# STB_FanControl.net
KiCad netlist of a schematic drawn in Altium Designer
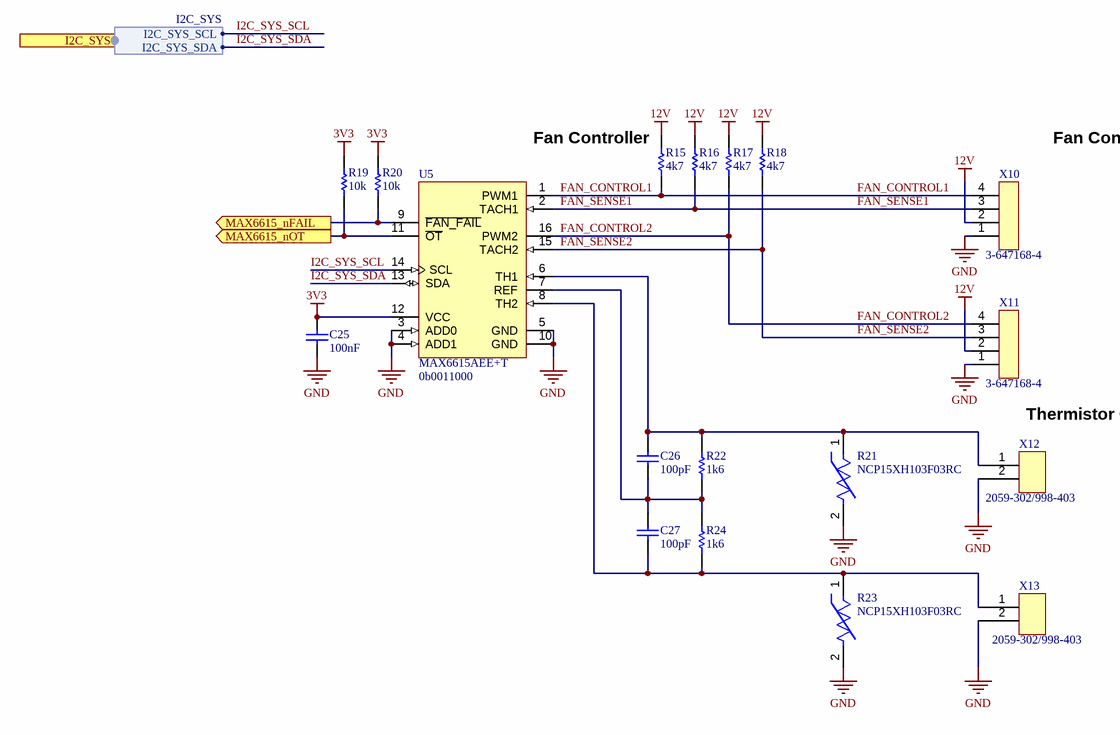
[diagram p0: STB_FanControl.SchDoc]

(export (version "E")
  (design (tool "Eeschema 10.0.6"))
  (components
    (comp (ref "C25")
      (value "100nF")
      (footprint "CAPC1050X55X23LL05T13")
      (description "Chip Capacitor, 100 nF, +/- 10%, 16 V, -55 to 125 degC, 0402 (1005 Metric), RoHS, Tape and Reel")
      (fields
        (field (name "MANUFACTURER") "Samsung Electro-Mechanics")
        (field (name "MANUFACTURER PART NUMBER") "CL05B104KO5NNNC")
      )
      (libsource (lib "Altium Content Vault") (part "CAP-NP-2"))
    )
    (comp (ref "C26")
      (value "100pF")
      (footprint "CAPC1005X56X25LL10T15")
      (fields
        (field (name "MANUFACTURER") "AVX Interconnect / Elco")
        (field (name "PART NUMBER") "04023A101KAT2A")
      )
      (libsource (lib "Altium Content Vault") (part "CAP"))
    )
    (comp (ref "C27")
      (value "100pF")
      (footprint "CAPC1005X56X25LL10T15")
      (fields
        (field (name "MANUFACTURER") "AVX Interconnect / Elco")
        (field (name "PART NUMBER") "04023A101KAT2A")
      )
      (libsource (lib "Altium Content Vault") (part "CAP"))
    )
    (comp (ref "R15")
      (value "4k7")
      (footprint "RESC1005X40X25LL05T10")
      (fields
        (field (name "MANUFACTURER") "Yageo / Phycomp")
        (field (name "PART NUMBER") "RC0402FR-074K7L")
        (field (name "TOLERANCE") "1%")
      )
      (libsource (lib "Altium Content Vault") (part "RES"))
    )
    (comp (ref "R16")
      (value "4k7")
      (footprint "RESC1005X40X25LL05T10")
      (fields
        (field (name "MANUFACTURER") "Yageo / Phycomp")
        (field (name "PART NUMBER") "RC0402FR-074K7L")
        (field (name "TOLERANCE") "1%")
      )
      (libsource (lib "Altium Content Vault") (part "RES"))
    )
    (comp (ref "R17")
      (value "4k7")
      (footprint "RESC1005X40X25LL05T10")
      (fields
        (field (name "MANUFACTURER") "Yageo / Phycomp")
        (field (name "PART NUMBER") "RC0402FR-074K7L")
        (field (name "TOLERANCE") "1%")
      )
      (libsource (lib "Altium Content Vault") (part "RES"))
    )
    (comp (ref "R18")
      (value "4k7")
      (footprint "RESC1005X40X25LL05T10")
      (fields
        (field (name "MANUFACTURER") "Yageo / Phycomp")
        (field (name "PART NUMBER") "RC0402FR-074K7L")
        (field (name "TOLERANCE") "1%")
      )
      (libsource (lib "Altium Content Vault") (part "RES"))
    )
    (comp (ref "R19")
      (value "10k")
      (footprint "RESC1005X40X25LL05T05")
      (description "Chip Resistor, 10 KOhm, +/- 1%, 0.1 W, -55 to 155 degC, 0402 (1005 Metric), RoHS, Tape and Reel")
      (fields (field (name "TOLERANCE") "1%") (field (name "MANUFACTURER") "Panasonic"))
      (libsource (lib "Altium Content Vault") (part "RES-2"))
    )
    (comp (ref "R20")
      (value "10k")
      (footprint "RESC1005X40X25LL05T05")
      (description "Chip Resistor, 10 KOhm, +/- 1%, 0.1 W, -55 to 155 degC, 0402 (1005 Metric), RoHS, Tape and Reel")
      (fields (field (name "TOLERANCE") "1%") (field (name "MANUFACTURER") "Panasonic"))
      (libsource (lib "Altium Content Vault") (part "RES-2"))
    )
    (comp (ref "R21")
      (value "NCP15XH103F03RC")
      (footprint "FP-NCP15-NCU15-0_05-IPC_C")
      (description "NTC Thermistor for Temperature Sensor, 0402, 10kΩ, 1%, 0.1mA, 5V")
      (fields (field (name "TOLERANCE") "1%") (field (name "MANUFACTURER") "Murata"))
      (libsource (lib "Altium Content Vault") (part "3b148a6ebabc5fb4d708a66c052d352"))
    )
    (comp (ref "R22")
      (value "1k6")
      (footprint "RESC1005X40X25LL05T10")
      (fields
        (field (name "MANUFACTURER") "Yageo / Phycomp")
        (field (name "PART NUMBER") "RC0402FR-071K6L")
        (field (name "TOLERANCE") "1%")
      )
      (libsource (lib "Altium Content Vault") (part "RES"))
    )
    (comp (ref "R23")
      (value "NCP15XH103F03RC")
      (footprint "FP-NCP15-NCU15-0_05-IPC_C")
      (description "NTC Thermistor for Temperature Sensor, 0402, 10kΩ, 1%, 0.1mA, 5V")
      (fields (field (name "TOLERANCE") "1%") (field (name "MANUFACTURER") "Murata"))
      (libsource (lib "Altium Content Vault") (part "3b148a6ebabc5fb4d708a66c052d352"))
    )
    (comp (ref "R24")
      (value "1k6")
      (footprint "RESC1005X40X25LL05T10")
      (fields
        (field (name "MANUFACTURER") "Yageo / Phycomp")
        (field (name "PART NUMBER") "RC0402FR-071K6L")
        (field (name "TOLERANCE") "1%")
      )
      (libsource (lib "Altium Content Vault") (part "RES"))
    )
    (comp (ref "U5")
      (value "MAX6615AEE+T")
      (footprint "MAXM-E16+1_M")
      (fields (field (name "GENERIC PART NUMBER") "MAX6615") (field (name "MANUFACTURER") "Maxim"))
      (libsource (lib "Altium Content Vault") (part "MAX6615-E16X1"))
    )
    (comp (ref "X10")
      (value "3-647168-4")
      (footprint "3-647168-4")
      (fields
        (field (name "MANUFACTURER") "TE Connectivity")
        (field (name "MANUFACTURER PART NUMBER") "3-647166-4")
      )
      (libsource (lib "STB_Schlib") (part "3-647168-4"))
    )
    (comp (ref "X11")
      (value "3-647168-4")
      (footprint "3-647168-4")
      (fields
        (field (name "MANUFACTURER") "TE Connectivity")
        (field (name "MANUFACTURER PART NUMBER") "3-647166-4")
      )
      (libsource (lib "STB_Schlib") (part "3-647168-4"))
    )
    (comp (ref "X12")
      (value "2059-302/998-403")
      (footprint "2059-302/998-403")
      (description "Barrier Strip Terminal Block, 3A, 0.34mm2, 1 Row(s), 1 Deck(s)")
      (fields (field (name "MANUFACTURER") "WAGO") (field (name "SAFETY APPROVAL") "UL"))
      (libsource (lib "STB_Schlib") (part "2059-302/998-403"))
    )
    (comp (ref "X13")
      (value "2059-302/998-403")
      (footprint "2059-302/998-403")
      (description "Barrier Strip Terminal Block, 3A, 0.34mm2, 1 Row(s), 1 Deck(s)")
      (fields (field (name "MANUFACTURER") "WAGO") (field (name "SAFETY APPROVAL") "UL"))
      (libsource (lib "STB_Schlib") (part "2059-302/998-403"))
    )
  )
  (nets
    (net (code "2") (name "/FAN_CONTROL1") (class "Default")
      (node (ref "R15") (pin "1") (pinfunction "1_1") (pintype "passive"))
      (node (ref "U5") (pin "1") (pinfunction "PWM1_1") (pintype "open_collector"))
      (node (ref "X10") (pin "4") (pintype "passive"))
    )
    (net (code "3") (name "/FAN_CONTROL2") (class "Default")
      (node (ref "R17") (pin "1") (pinfunction "1_1") (pintype "passive"))
      (node (ref "U5") (pin "16") (pinfunction "PWM2_16") (pintype "open_collector"))
      (node (ref "X11") (pin "4") (pintype "passive"))
    )
    (net (code "4") (name "/FAN_SENSE1") (class "Default")
      (node (ref "R16") (pin "1") (pinfunction "1_1") (pintype "passive"))
      (node (ref "U5") (pin "2") (pinfunction "TACH1_2") (pintype "input"))
      (node (ref "X10") (pin "3") (pintype "passive"))
    )
    (net (code "5") (name "/FAN_SENSE2") (class "Default")
      (node (ref "R18") (pin "1") (pinfunction "1_1") (pintype "passive"))
      (node (ref "U5") (pin "15") (pinfunction "TACH2_15") (pintype "input"))
      (node (ref "X11") (pin "3") (pintype "passive"))
    )
    (net (code "6") (name "/I2C_SYS_SCL") (class "Default")
      (node (ref "U5") (pin "14") (pinfunction "SCL_14") (pintype "input"))
    )
    (net (code "7") (name "/I2C_SYS_SDA") (class "Default")
      (node (ref "U5") (pin "13") (pinfunction "SDA_13") (pintype "bidirectional"))
    )
    (net (code "8") (name "/MAX6615_nFAIL") (class "Default")
      (node (ref "R20") (pin "1") (pinfunction "1_1") (pintype "passive"))
      (node (ref "U5") (pin "9") (pinfunction "~{FAN_FAIL}_9") (pintype "tri_state"))
    )
    (net (code "9") (name "/MAX6615_nOT") (class "Default")
      (node (ref "R19") (pin "1") (pinfunction "1_1") (pintype "passive"))
      (node (ref "U5") (pin "11") (pinfunction "~{OT}_11") (pintype "tri_state"))
    )
    (net (code "11") (name "3V3") (class "Default")
      (node (ref "C25") (pin "2") (pinfunction "2_2") (pintype "passive"))
      (node (ref "R19") (pin "2") (pinfunction "2_2") (pintype "passive"))
      (node (ref "R20") (pin "2") (pinfunction "2_2") (pintype "passive"))
      (node (ref "U5") (pin "12") (pinfunction "VCC_12") (pintype "power_in"))
    )
    (net (code "12") (name "12V") (class "Default")
      (node (ref "R15") (pin "2") (pinfunction "2_2") (pintype "passive"))
      (node (ref "R16") (pin "2") (pinfunction "2_2") (pintype "passive"))
      (node (ref "R17") (pin "2") (pinfunction "2_2") (pintype "passive"))
      (node (ref "R18") (pin "2") (pinfunction "2_2") (pintype "passive"))
      (node (ref "X10") (pin "2") (pintype "passive"))
      (node (ref "X11") (pin "2") (pintype "passive"))
    )
    (net (code "13") (name "GND") (class "Default")
      (node (ref "C25") (pin "1") (pinfunction "1_1") (pintype "passive"))
      (node (ref "R21") (pin "2") (pinfunction "2_2") (pintype "passive"))
      (node (ref "R23") (pin "2") (pinfunction "2_2") (pintype "passive"))
      (node (ref "U5") (pin "10") (pinfunction "GND_10") (pintype "power_in"))
      (node (ref "U5") (pin "3") (pinfunction "ADD0_3") (pintype "input"))
      (node (ref "U5") (pin "4") (pinfunction "ADD1_4") (pintype "input"))
      (node (ref "U5") (pin "5") (pinfunction "GND_5") (pintype "power_in"))
      (node (ref "X10") (pin "1") (pintype "passive"))
      (node (ref "X11") (pin "1") (pintype "passive"))
      (node (ref "X12") (pin "2") (pintype "passive"))
      (node (ref "X13") (pin "2") (pintype "passive"))
    )
    (net (code "14") (name "Net-(U5-REF)") (class "Default")
      (node (ref "C26") (pin "1") (pinfunction "1_1") (pintype "passive"))
      (node (ref "C27") (pin "2") (pinfunction "2_2") (pintype "passive"))
      (node (ref "R22") (pin "1") (pinfunction "1_1") (pintype "passive"))
      (node (ref "R24") (pin "2") (pinfunction "2_2") (pintype "passive"))
      (node (ref "U5") (pin "7") (pinfunction "REF_7") (pintype "tri_state"))
    )
    (net (code "15") (name "Net-(U5-TH1)") (class "Default")
      (node (ref "C26") (pin "2") (pinfunction "2_2") (pintype "passive"))
      (node (ref "R21") (pin "1") (pinfunction "1_1") (pintype "passive"))
      (node (ref "R22") (pin "2") (pinfunction "2_2") (pintype "passive"))
      (node (ref "U5") (pin "6") (pinfunction "TH1_6") (pintype "input"))
      (node (ref "X12") (pin "1") (pintype "passive"))
    )
    (net (code "16") (name "Net-(U5-TH2)") (class "Default")
      (node (ref "C27") (pin "1") (pinfunction "1_1") (pintype "passive"))
      (node (ref "R23") (pin "1") (pinfunction "1_1") (pintype "passive"))
      (node (ref "R24") (pin "1") (pinfunction "1_1") (pintype "passive"))
      (node (ref "U5") (pin "8") (pinfunction "TH2_8") (pintype "input"))
      (node (ref "X13") (pin "1") (pintype "passive"))
    )
  )
)
